# IO_Peripherals.net
KiCad netlist of a schematic drawn in Altium Designer
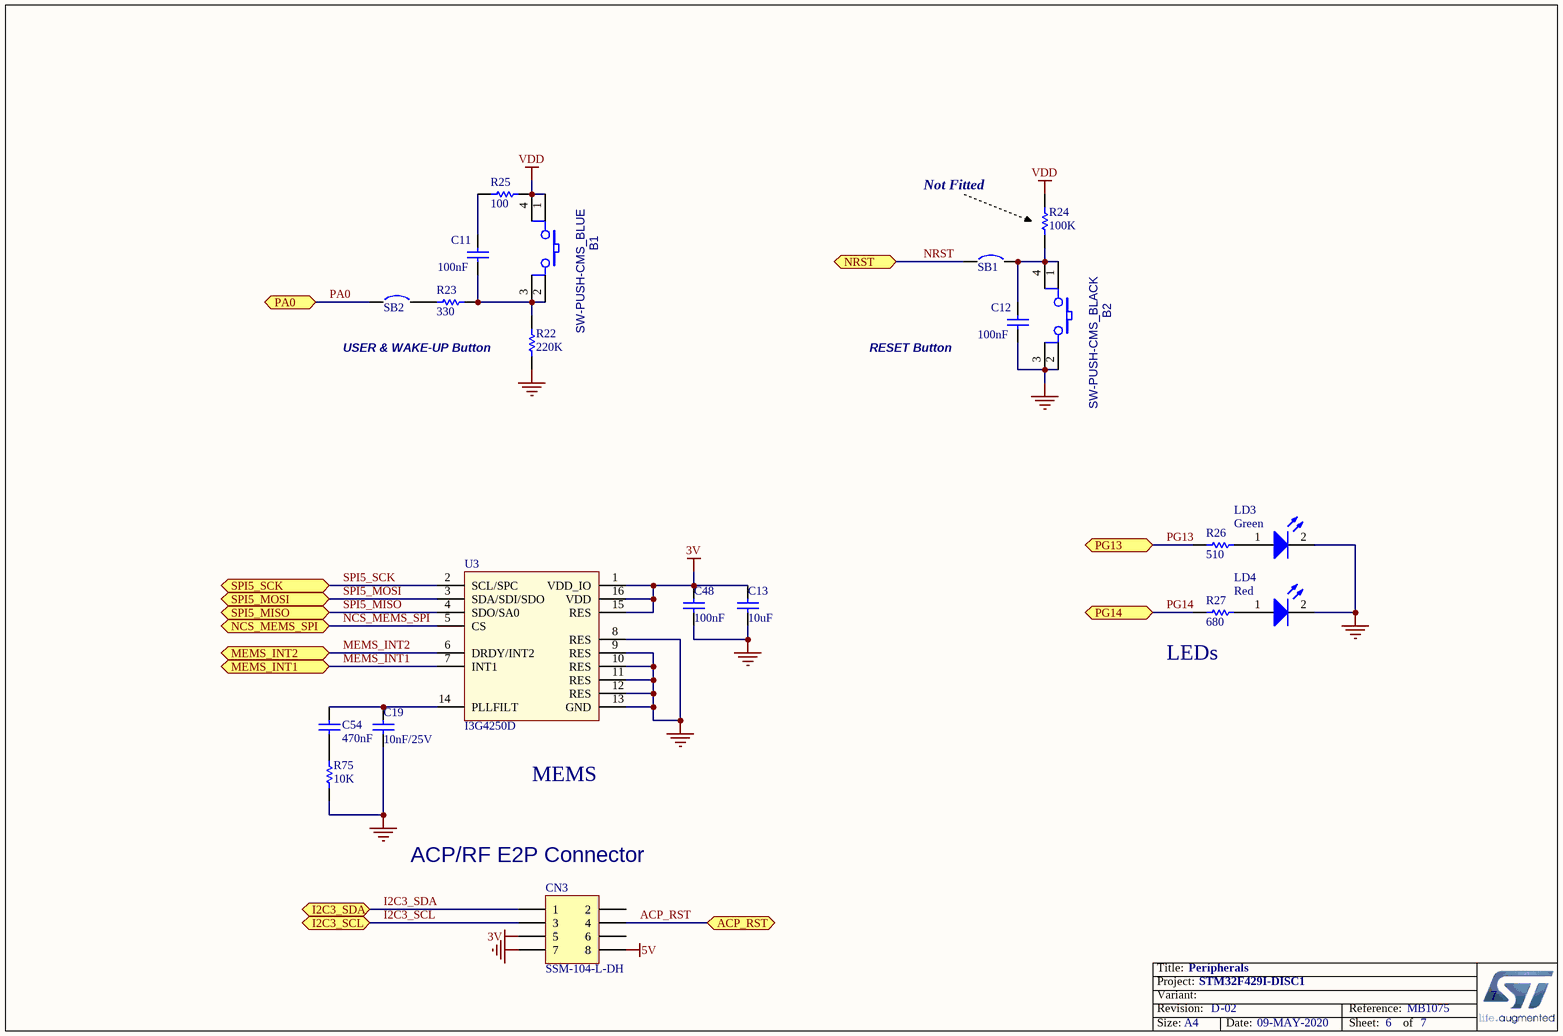
[diagram p0: IO Peripherals.SchDoc]

(export (version "E")
  (design (tool "Eeschema 10.0.6"))
  (components
    (comp (ref "B1")
      (value "SW-PUSH-CMS_BLUE")
      (footprint "BP1CMS")
      (description "Non-Open Push-Button 0.1A 24V")
      (libsource (lib "MCD_TOOLS") (part "SW-PUSH-CMS_BLUE"))
    )
    (comp (ref "B2")
      (value "SW-PUSH-CMS_BLACK")
      (footprint "BP1CMS")
      (description "Non-Open Push-Button 0.1A 24V")
      (libsource (lib "MCD_TOOLS") (part "SW-PUSH-CMS_BLACK"))
    )
    (comp (ref "C11")
      (value "100nF")
      (footprint "0402C")
      (description "Capacitor 0402 / 0603 / 0805")
      (libsource (lib "MCD_TOOLS") (part "Capacitor_ST"))
    )
    (comp (ref "C12")
      (value "100nF")
      (footprint "0402C")
      (description "Capacitor 0402 / 0603 / 0805")
      (libsource (lib "MCD_TOOLS") (part "Capacitor_ST"))
    )
    (comp (ref "C13")
      (value "10uF")
      (footprint "0603C")
      (description "Capacitor")
      (fields (field (name "PUBLISHER") "Altium Limited"))
      (libsource (lib "Miscellaneous Devices") (part "CAP"))
    )
    (comp (ref "C19")
      (value "10nF/25V")
      (footprint "0603C")
      (description "Capacitor")
      (fields (field (name "PUBLISHER") "Altium Limited"))
      (libsource (lib "Miscellaneous Devices") (part "CAP"))
    )
    (comp (ref "C48")
      (value "100nF")
      (footprint "0402C")
      (description "Capacitor 0402 / 0603 / 0805")
      (libsource (lib "MCD_TOOLS") (part "Capacitor_ST"))
    )
    (comp (ref "C54")
      (value "470nF")
      (footprint "C0603")
      (description "Capacitor, MLCC, 470nF, 16V, X7R, 10%, 0603, T=0.8mm")
      (fields
        (field (name "INTERNAL_PART_NUMBER") "MCD-01006")
        (field (name "MANUFACTURER_PART_NUMBER") "CC0603KRX7R7BB474")
        (field (name "PROVIDED_BY") "SUBCO")
      )
      (libsource (lib "MCD_PARTS_database") (part "Capacitor"))
    )
    (comp (ref "CN3")
      (value "SSM-104-L-DH")
      (footprint "SSM-104-L-DH")
      (description "Header, 5-Pin, Dual row")
      (fields (field (name "PUBLISHER") "Altium Limited"))
      (libsource (lib "mb1045") (part "SSM-104-L-DH"))
    )
    (comp (ref "LD3")
      (value "Green")
      (footprint "0603D")
      (description "Typical RED, GREEN, YELLOW, AMBER GaAs LED")
      (fields (field (name "PUBLISHER") "Altium Limited"))
      (libsource (lib "Miscellaneous Devices") (part "LED2"))
    )
    (comp (ref "LD4")
      (value "Red")
      (footprint "0603D")
      (description "Typical RED, GREEN, YELLOW, AMBER GaAs LED")
      (fields (field (name "PUBLISHER") "Altium Limited"))
      (libsource (lib "Miscellaneous Devices") (part "LED2"))
    )
    (comp (ref "R22")
      (value "220K")
      (footprint "0402R")
      (description "Resistor 0402 / 0603 / 0805")
      (libsource (lib "MCD_TOOLS") (part "Resistor_ST"))
    )
    (comp (ref "R23")
      (value "330")
      (footprint "0402R")
      (description "Resistor 0402 / 0603 / 0805")
      (libsource (lib "MCD_TOOLS") (part "Resistor_ST"))
    )
    (comp (ref "R24")
      (value "100K")
      (footprint "0402R")
      (description "Resistor 0402 / 0603 / 0805")
      (libsource (lib "MCD_TOOLS") (part "Resistor_ST"))
    )
    (comp (ref "R25")
      (value "100")
      (footprint "0402R")
      (description "Resistor 0402 / 0603 / 0805")
      (libsource (lib "MCD_TOOLS") (part "Resistor_ST"))
    )
    (comp (ref "R26")
      (value "510")
      (footprint "0603R")
      (description "Resistor 0402 / 0603 / 0805")
      (libsource (lib "MCD_TOOLS") (part "Resistor_ST"))
    )
    (comp (ref "R27")
      (value "680")
      (footprint "0603R")
      (description "Resistor 0402 / 0603 / 0805")
      (libsource (lib "MCD_TOOLS") (part "Resistor_ST"))
    )
    (comp (ref "R75")
      (value "10K")
      (footprint "0402R")
      (description "Resistor 0402 / 0603 / 0805")
      (libsource (lib "MCD_TOOLS") (part "Resistor_ST"))
    )
    (comp (ref "SB1")
      (value "Circuit Breaker")
      (footprint "JP2_SMD")
      (fields (field (name "PUBLISHER") "Altium Limited"))
      (libsource (lib "MB915") (part "Circuit Breaker"))
    )
    (comp (ref "SB2")
      (value "Circuit Breaker")
      (footprint "JP2_SMD")
      (fields (field (name "PUBLISHER") "Altium Limited"))
      (libsource (lib "MB915") (part "Circuit Breaker"))
    )
    (comp (ref "U3")
      (value "I3G4250D")
      (footprint "ICC_LGA16_4X4_P065_H1P1")
      (description "MEMS motion sensor: 3-axis digital output gyroscope LG4-16 4x4mm")
      (fields
        (field (name "INTERNAL_PART_NUMBER") "MCD-01963")
        (field (name "MANUFACTURER") "STMICROELECTRONICS")
        (field (name "PROVIDED_BY") "SUBCO with ST control")
      )
      (libsource (lib "MCD_PARTS_database") (part "I3G4250D"))
    )
  )
  (nets
    (net (code "1") (name "/ACP_RST") (class "Default")
      (node (ref "CN3") (pin "4") (pinfunction "4_4") (pintype "passive"))
    )
    (net (code "2") (name "/I2C3_SCL") (class "Default")
      (node (ref "CN3") (pin "3") (pinfunction "3_3") (pintype "passive"))
    )
    (net (code "3") (name "/I2C3_SDA") (class "Default")
      (node (ref "CN3") (pin "1") (pinfunction "1_1") (pintype "passive"))
    )
    (net (code "4") (name "/MEMS_INT1") (class "Default")
      (node (ref "U3") (pin "7") (pinfunction "INT1_7") (pintype "passive"))
    )
    (net (code "5") (name "/MEMS_INT2") (class "Default")
      (node (ref "U3") (pin "6") (pinfunction "DRDY/INT2_6") (pintype "passive"))
    )
    (net (code "6") (name "/NCS_MEMS_SPI") (class "Default")
      (node (ref "U3") (pin "5") (pinfunction "CS_5") (pintype "passive"))
    )
    (net (code "7") (name "/NRST") (class "Default")
      (node (ref "SB1") (pin "1") (pinfunction "1_1") (pintype "passive"))
    )
    (net (code "8") (name "/PA0") (class "Default")
      (node (ref "SB2") (pin "1") (pinfunction "1_1") (pintype "passive"))
    )
    (net (code "9") (name "/PG13") (class "Default")
      (node (ref "R26") (pin "1") (pinfunction "1_1") (pintype "passive"))
    )
    (net (code "10") (name "/PG14") (class "Default")
      (node (ref "R27") (pin "1") (pinfunction "1_1") (pintype "passive"))
    )
    (net (code "11") (name "/SPI5_MISO") (class "Default")
      (node (ref "U3") (pin "4") (pinfunction "SDO/SA0_4") (pintype "passive"))
    )
    (net (code "12") (name "/SPI5_MOSI") (class "Default")
      (node (ref "U3") (pin "3") (pinfunction "SDA/SDI/SDO_3") (pintype "passive"))
    )
    (net (code "13") (name "/SPI5_SCK") (class "Default")
      (node (ref "U3") (pin "2") (pinfunction "SCL/SPC_2") (pintype "passive"))
    )
    (net (code "14") (name "3V") (class "Default")
      (node (ref "C13") (pin "2") (pinfunction "2_2") (pintype "passive"))
      (node (ref "C48") (pin "2") (pinfunction "2_2") (pintype "passive"))
      (node (ref "CN3") (pin "5") (pinfunction "5_5") (pintype "passive"))
      (node (ref "U3") (pin "1") (pinfunction "VDD_IO_1") (pintype "passive"))
      (node (ref "U3") (pin "15") (pinfunction "RES_15") (pintype "passive"))
      (node (ref "U3") (pin "16") (pinfunction "VDD_16") (pintype "passive"))
    )
    (net (code "15") (name "5V") (class "Default")
      (node (ref "CN3") (pin "8") (pinfunction "8_8") (pintype "passive"))
    )
    (net (code "16") (name "GND") (class "Default")
      (node (ref "B2") (pin "2") (pinfunction "2_2") (pintype "passive"))
      (node (ref "B2") (pin "3") (pinfunction "3_3") (pintype "passive"))
      (node (ref "C12") (pin "1") (pinfunction "1_1") (pintype "passive"))
      (node (ref "C13") (pin "1") (pinfunction "1_1") (pintype "passive"))
      (node (ref "C19") (pin "1") (pinfunction "1_1") (pintype "passive"))
      (node (ref "C48") (pin "1") (pinfunction "1_1") (pintype "passive"))
      (node (ref "CN3") (pin "7") (pinfunction "7_7") (pintype "passive"))
      (node (ref "LD3") (pin "2") (pinfunction "K_2") (pintype "passive"))
      (node (ref "LD4") (pin "2") (pinfunction "K_2") (pintype "passive"))
      (node (ref "R22") (pin "1") (pinfunction "1_1") (pintype "passive"))
      (node (ref "R75") (pin "1") (pinfunction "1_1") (pintype "passive"))
      (node (ref "U3") (pin "10") (pinfunction "RES_10") (pintype "passive"))
      (node (ref "U3") (pin "11") (pinfunction "RES_11") (pintype "passive"))
      (node (ref "U3") (pin "12") (pinfunction "RES_12") (pintype "passive"))
      (node (ref "U3") (pin "13") (pinfunction "GND_13") (pintype "passive"))
      (node (ref "U3") (pin "8") (pinfunction "RES_8") (pintype "passive"))
      (node (ref "U3") (pin "9") (pinfunction "RES_9") (pintype "passive"))
    )
    (net (code "17") (name "Net-(B1-Pad2)") (class "Default")
      (node (ref "B1") (pin "2") (pinfunction "2_2") (pintype "passive"))
      (node (ref "B1") (pin "3") (pinfunction "3_3") (pintype "passive"))
      (node (ref "C11") (pin "1") (pinfunction "1_1") (pintype "passive"))
      (node (ref "R22") (pin "2") (pinfunction "2_2") (pintype "passive"))
      (node (ref "R23") (pin "2") (pinfunction "2_2") (pintype "passive"))
    )
    (net (code "18") (name "Net-(B2-Pad1)") (class "Default")
      (node (ref "B2") (pin "1") (pinfunction "1_1") (pintype "passive"))
      (node (ref "B2") (pin "4") (pinfunction "4_4") (pintype "passive"))
      (node (ref "C12") (pin "2") (pinfunction "2_2") (pintype "passive"))
      (node (ref "R24") (pin "1") (pinfunction "1_1") (pintype "passive"))
      (node (ref "SB1") (pin "2") (pinfunction "2_2") (pintype "passive"))
    )
    (net (code "19") (name "Net-(C11-Pad2)") (class "Default")
      (node (ref "C11") (pin "2") (pinfunction "2_2") (pintype "passive"))
      (node (ref "R25") (pin "1") (pinfunction "1_1") (pintype "passive"))
    )
    (net (code "20") (name "Net-(C54-Pad1)") (class "Default")
      (node (ref "C54") (pin "1") (pinfunction "1_1") (pintype "passive"))
      (node (ref "R75") (pin "2") (pinfunction "2_2") (pintype "passive"))
    )
    (net (code "21") (name "Net-(LD3-A)") (class "Default")
      (node (ref "LD3") (pin "1") (pinfunction "A_1") (pintype "passive"))
      (node (ref "R26") (pin "2") (pinfunction "2_2") (pintype "passive"))
    )
    (net (code "22") (name "Net-(LD4-A)") (class "Default")
      (node (ref "LD4") (pin "1") (pinfunction "A_1") (pintype "passive"))
      (node (ref "R27") (pin "2") (pinfunction "2_2") (pintype "passive"))
    )
    (net (code "23") (name "Net-(R23-Pad1)") (class "Default")
      (node (ref "R23") (pin "1") (pinfunction "1_1") (pintype "passive"))
      (node (ref "SB2") (pin "2") (pinfunction "2_2") (pintype "passive"))
    )
    (net (code "24") (name "Net-(U3-PLLFILT)") (class "Default")
      (node (ref "C19") (pin "2") (pinfunction "2_2") (pintype "passive"))
      (node (ref "C54") (pin "2") (pinfunction "2_2") (pintype "passive"))
      (node (ref "U3") (pin "14") (pinfunction "PLLFILT_14") (pintype "passive"))
    )
    (net (code "25") (name "VDD") (class "Default")
      (node (ref "B1") (pin "1") (pinfunction "1_1") (pintype "passive"))
      (node (ref "B1") (pin "4") (pinfunction "4_4") (pintype "passive"))
      (node (ref "R24") (pin "2") (pinfunction "2_2") (pintype "passive"))
      (node (ref "R25") (pin "2") (pinfunction "2_2") (pintype "passive"))
    )
    (net (code "26") (name "unconnected-(CN3-Pad2)") (class "Default")
      (node (ref "CN3") (pin "2") (pinfunction "2_2") (pintype "passive"))
    )
    (net (code "27") (name "unconnected-(CN3-Pad6)") (class "Default")
      (node (ref "CN3") (pin "6") (pinfunction "6_6") (pintype "passive"))
    )
  )
)
